# esp_tiny1.net
KiCad netlist of a schematic drawn in EAGLE
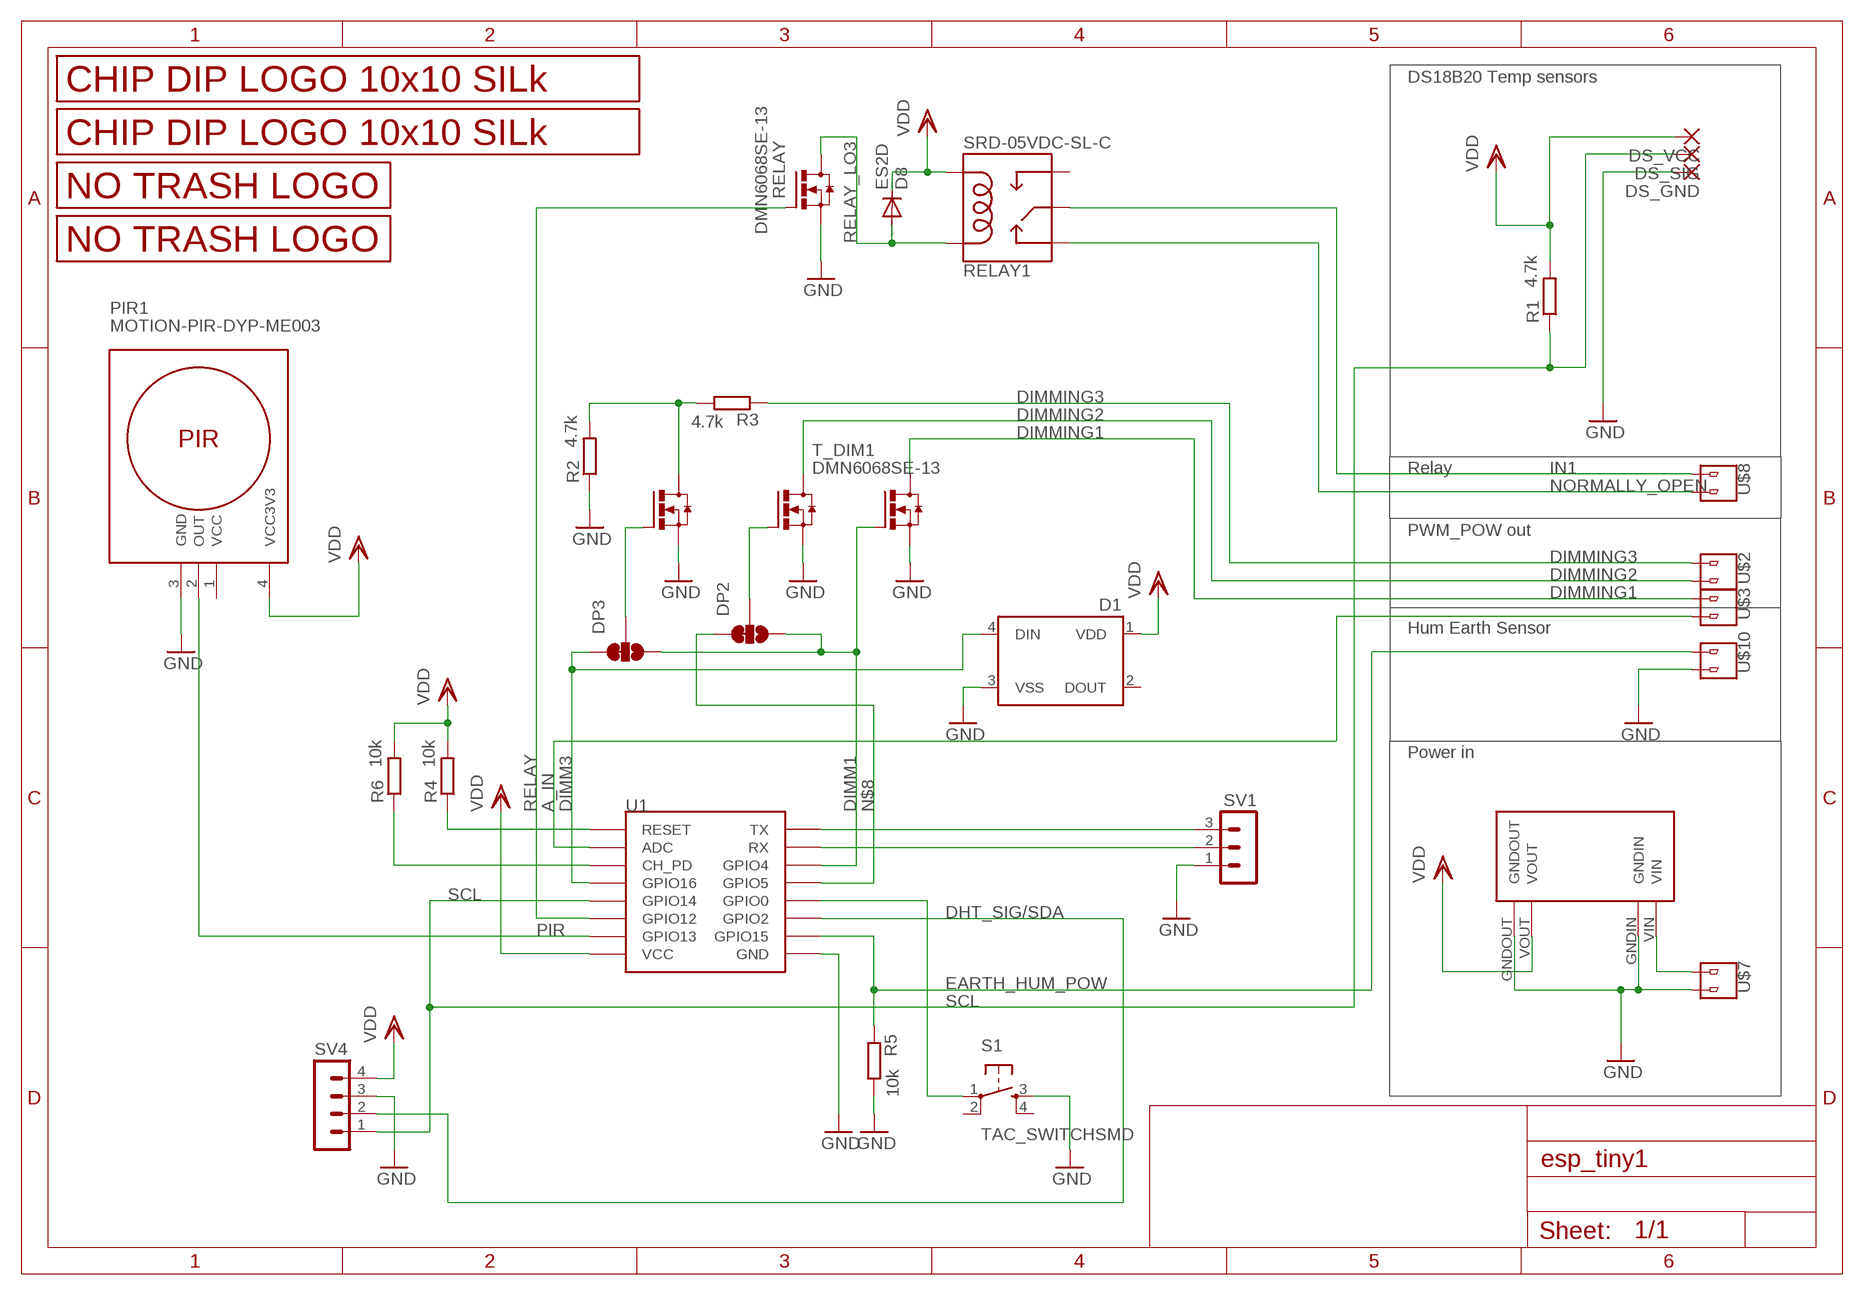
[diagram p0: schematic, sheet 1]

(export (version "E")
  (design (tool "Eeschema 10.0.6"))
  (components
    (comp (ref "D1")
      (value "WS2812B")
      (footprint "eagle-import:WS2812B")
      (libsource (lib "eagle-import") (part "WS2812B"))
    )
    (comp (ref "D8")
      (value "ES2D")
      (footprint "eagle-import:SMB")
      (libsource (lib "eagle-import") (part "DIODE-SMB"))
    )
    (comp (ref "DP2")
      (value "SMD_SJ_3WAY_CLOSED")
      (footprint "eagle-import:SMD_SJ_3WAY_CLOSED")
      (libsource (lib "eagle-import") (part "SMD_SJ_3WAY_CLOSED"))
    )
    (comp (ref "DP3")
      (value "SMD_SJ_3WAY_CLOSED")
      (footprint "eagle-import:SMD_SJ_3WAY_CLOSED")
      (libsource (lib "eagle-import") (part "SMD_SJ_3WAY_CLOSED"))
    )
    (comp (ref "DS_GND")
      (value "SMD2")
      (footprint "eagle-import:SMD1,27-2,54")
      (libsource (lib "eagle-import") (part "SMD2"))
    )
    (comp (ref "DS_SIG")
      (value "SMD2")
      (footprint "eagle-import:SMD1,27-2,54")
      (libsource (lib "eagle-import") (part "SMD2"))
    )
    (comp (ref "DS_VCC")
      (value "SMD2")
      (footprint "eagle-import:SMD1,27-2,54")
      (libsource (lib "eagle-import") (part "SMD2"))
    )
    (comp (ref "PIR1")
      (value "MOTION-PIR-DYP-ME003")
      (footprint "eagle-import:MOTION-PIR-DYP-ME003_FRAMELESS")
      (libsource (lib "eagle-import") (part "MOTION-PIR-DYP-ME003"))
    )
    (comp (ref "R1")
      (value "4.7k")
      (footprint "eagle-import:M0805")
      (libsource (lib "eagle-import") (part "R-EU_M0805"))
    )
    (comp (ref "R2")
      (value "4.7k")
      (footprint "eagle-import:M0805")
      (libsource (lib "eagle-import") (part "R-EU_M0805"))
    )
    (comp (ref "R3")
      (value "4.7k")
      (footprint "eagle-import:M0805")
      (libsource (lib "eagle-import") (part "R-EU_M0805"))
    )
    (comp (ref "R4")
      (value "10k")
      (footprint "eagle-import:M0805")
      (libsource (lib "eagle-import") (part "R-EU_M0805"))
    )
    (comp (ref "R5")
      (value "10k")
      (footprint "eagle-import:M0805")
      (libsource (lib "eagle-import") (part "R-EU_M0805"))
    )
    (comp (ref "R6")
      (value "10k")
      (footprint "eagle-import:M0805")
      (libsource (lib "eagle-import") (part "R-EU_M0805"))
    )
    (comp (ref "RELAY")
      (value "DMN6068SE-13")
      (footprint "eagle-import:SOT223")
      (libsource (lib "eagle-import") (part "NMOSFET_SMD_223"))
    )
    (comp (ref "RELAY1")
      (value "SRD-05VDC-SL-C")
      (footprint "eagle-import:SRD-05VDC-SL-C")
      (libsource (lib "eagle-import") (part "RELAYPTH"))
    )
    (comp (ref "S1")
      (value "TAC_SWITCHSMD")
      (footprint "eagle-import:TACTILE-SWITCH-SMD")
      (libsource (lib "eagle-import") (part "TAC_SWITCHSMD"))
    )
    (comp (ref "SV1")
      (value "MA03-1")
      (footprint "eagle-import:MA03-1")
      (libsource (lib "eagle-import") (part "MA03-1"))
    )
    (comp (ref "SV4")
      (value "MA04-1")
      (footprint "eagle-import:MA04-1")
      (libsource (lib "eagle-import") (part "MA04-1"))
    )
    (comp (ref "T_DIM1")
      (value "DMN6068SE-13")
      (footprint "eagle-import:SOT223")
      (libsource (lib "eagle-import") (part "NMOSFET_SMD_223"))
    )
    (comp (ref "T_DIM2")
      (value "DMN6068SE-13")
      (footprint "eagle-import:SOT223")
      (libsource (lib "eagle-import") (part "NMOSFET_SMD_223"))
    )
    (comp (ref "T_DIM3")
      (value "DMN6068SE-13")
      (footprint "eagle-import:SOT223")
      (libsource (lib "eagle-import") (part "NMOSFET_SMD_223"))
    )
    (comp (ref "U$1")
      (value "LOGO_10X10_SILK")
      (footprint "eagle-import:LOGO2_10X10_SILK")
      (libsource (lib "eagle-import") (part "LOGO_10X10_SILK"))
    )
    (comp (ref "U$2")
      (value "V1")
      (footprint "eagle-import:2_SCREW_PIN")
      (libsource (lib "eagle-import") (part "2_PIN_CONNECTOR"))
    )
    (comp (ref "U$3")
      (value "V1")
      (footprint "eagle-import:2_SCREW_PIN")
      (libsource (lib "eagle-import") (part "2_PIN_CONNECTOR"))
    )
    (comp (ref "U$4")
      (value "LOGO_NO_TRASHNO_TRASH")
      (footprint "eagle-import:LOGO_ROHS_NO_TRASH")
      (libsource (lib "eagle-import") (part "LOGO_NO_TRASHNO_TRASH"))
    )
    (comp (ref "U$7")
      (value "V1")
      (footprint "eagle-import:2_SCREW_PIN")
      (libsource (lib "eagle-import") (part "2_PIN_CONNECTOR"))
    )
    (comp (ref "U$8")
      (value "V1")
      (footprint "eagle-import:2_SCREW_PIN")
      (libsource (lib "eagle-import") (part "2_PIN_CONNECTOR"))
    )
    (comp (ref "U$9")
      (value "LOGO_NO_TRASHROHS")
      (footprint "eagle-import:LOGO_ROHS_SYM")
      (libsource (lib "eagle-import") (part "LOGO_NO_TRASHROHS"))
    )
    (comp (ref "U$10")
      (value "V1")
      (footprint "eagle-import:2_SCREW_PIN")
      (libsource (lib "eagle-import") (part "2_PIN_CONNECTOR"))
    )
    (comp (ref "U$11")
      (value "LOGO_10X10_SILK")
      (footprint "eagle-import:LOGO2_10X10_SILK")
      (libsource (lib "eagle-import") (part "LOGO_10X10_SILK"))
    )
    (comp (ref "U$12")
      (value "MP1584EN")
      (footprint "eagle-import:MP1584EN")
      (libsource (lib "eagle-import") (part "MP1584EN"))
    )
    (comp (ref "U1")
      (value "ESP12SMD")
      (footprint "eagle-import:ESP12-SMD")
      (libsource (lib "eagle-import") (part "ESP12SMD"))
    )
  )
  (nets
    (net (code "1") (name "/A_IN") (class "Default")
      (node (ref "U$3") (pin "P$2") (pinfunction "2_P$2") (pintype "passive"))
      (node (ref "U1") (pin "ADC") (pinfunction "ADC_ADC") (pintype "bidirectional"))
    )
    (net (code "2") (name "/DHT_SIG{slash}SDA") (class "Default")
      (node (ref "SV4") (pin "2") (pinfunction "2_2") (pintype "passive"))
      (node (ref "U1") (pin "GPIO2") (pinfunction "GPIO2_GPIO2") (pintype "bidirectional"))
    )
    (net (code "3") (name "/DIMM1") (class "Default")
      (node (ref "DP2") (pin "3") (pinfunction "3_3") (pintype "passive"))
      (node (ref "DP3") (pin "3") (pinfunction "3_3") (pintype "passive"))
      (node (ref "T_DIM1") (pin "1") (pinfunction "G_1") (pintype "passive"))
      (node (ref "U1") (pin "GPIO4") (pinfunction "GPIO4_GPIO4") (pintype "bidirectional"))
    )
    (net (code "4") (name "/DIMM3") (class "Default")
      (node (ref "D1") (pin "4") (pinfunction "DIN_4") (pintype "input"))
      (node (ref "DP3") (pin "1") (pinfunction "1_1") (pintype "passive"))
      (node (ref "U1") (pin "GPIO16") (pinfunction "GPIO16_GPIO16") (pintype "bidirectional"))
    )
    (net (code "5") (name "/DIMMING1") (class "Default")
      (node (ref "T_DIM1") (pin "2") (pinfunction "D_2") (pintype "passive"))
      (node (ref "T_DIM1") (pin "4") (pinfunction "D_4") (pintype "passive"))
      (node (ref "U$3") (pin "P$1") (pinfunction "1_P$1") (pintype "passive"))
    )
    (net (code "6") (name "/DIMMING2") (class "Default")
      (node (ref "T_DIM2") (pin "2") (pinfunction "D_2") (pintype "passive"))
      (node (ref "T_DIM2") (pin "4") (pinfunction "D_4") (pintype "passive"))
      (node (ref "U$2") (pin "P$2") (pinfunction "2_P$2") (pintype "passive"))
    )
    (net (code "7") (name "/DIMMING3") (class "Default")
      (node (ref "R3") (pin "1") (pinfunction "1_1") (pintype "passive"))
      (node (ref "U$2") (pin "P$1") (pinfunction "1_P$1") (pintype "passive"))
    )
    (net (code "8") (name "/EARTH_HUM_POW") (class "Default")
      (node (ref "R5") (pin "1") (pinfunction "1_1") (pintype "passive"))
      (node (ref "U$10") (pin "P$1") (pinfunction "1_P$1") (pintype "passive"))
      (node (ref "U1") (pin "GPIO15") (pinfunction "GPIO15_GPIO15") (pintype "bidirectional"))
    )
    (net (code "9") (name "/IN1") (class "Default")
      (node (ref "RELAY1") (pin "SWCOMMON") (pinfunction "SWCOMMON_SWCOMMON") (pintype "bidirectional"))
      (node (ref "U$8") (pin "P$1") (pinfunction "1_P$1") (pintype "passive"))
    )
    (net (code "10") (name "/N$8") (class "Default")
      (node (ref "DP2") (pin "1") (pinfunction "1_1") (pintype "passive"))
      (node (ref "U1") (pin "GPIO5") (pinfunction "GPIO5_GPIO5") (pintype "bidirectional"))
    )
    (net (code "11") (name "/NORMALLY_OPEN") (class "Default")
      (node (ref "RELAY1") (pin "SWCLOSED") (pinfunction "SWCLOSE_SWCLOSED") (pintype "bidirectional"))
      (node (ref "U$8") (pin "P$2") (pinfunction "2_P$2") (pintype "passive"))
    )
    (net (code "12") (name "/PIR") (class "Default")
      (node (ref "PIR1") (pin "2") (pinfunction "OUT_2") (pintype "output"))
      (node (ref "U1") (pin "GPIO13") (pinfunction "GPIO13_GPIO13") (pintype "bidirectional"))
    )
    (net (code "13") (name "/RELAY") (class "Default")
      (node (ref "RELAY") (pin "1") (pinfunction "G_1") (pintype "passive"))
      (node (ref "U1") (pin "GPIO12") (pinfunction "GPIO12_GPIO12") (pintype "bidirectional"))
    )
    (net (code "14") (name "/RELAY_LO3") (class "Default")
      (node (ref "D8") (pin "A") (pinfunction "A_A") (pintype "passive"))
      (node (ref "RELAY") (pin "2") (pinfunction "D_2") (pintype "passive"))
      (node (ref "RELAY") (pin "4") (pinfunction "D_4") (pintype "passive"))
      (node (ref "RELAY1") (pin "COIL1") (pinfunction "COIL1_COIL1") (pintype "bidirectional"))
    )
    (net (code "15") (name "/SCL") (class "Default")
      (node (ref "DS_SIG") (pin "1") (pinfunction "P_1") (pintype "passive"))
      (node (ref "R1") (pin "1") (pinfunction "1_1") (pintype "passive"))
      (node (ref "SV4") (pin "1") (pinfunction "1_1") (pintype "passive"))
      (node (ref "U1") (pin "GPIO14") (pinfunction "GPIO14_GPIO14") (pintype "bidirectional"))
    )
    (net (code "16") (name "/VCC") (class "Default")
      (node (ref "PIR1") (pin "1") (pinfunction "VCC_1") (pintype "power_in"))
    )
    (net (code "17") (name "GND") (class "Default")
      (node (ref "D1") (pin "3") (pinfunction "VSS_3") (pintype "power_in"))
      (node (ref "DS_GND") (pin "1") (pinfunction "P_1") (pintype "passive"))
      (node (ref "PIR1") (pin "3") (pinfunction "GND_3") (pintype "power_in"))
      (node (ref "R2") (pin "1") (pinfunction "1_1") (pintype "passive"))
      (node (ref "R5") (pin "2") (pinfunction "2_2") (pintype "passive"))
      (node (ref "RELAY") (pin "3") (pinfunction "S_3") (pintype "passive"))
      (node (ref "S1") (pin "3") (pinfunction "3_3") (pintype "passive"))
      (node (ref "SV1") (pin "1") (pinfunction "1_1") (pintype "passive"))
      (node (ref "SV4") (pin "3") (pinfunction "3_3") (pintype "passive"))
      (node (ref "T_DIM1") (pin "3") (pinfunction "S_3") (pintype "passive"))
      (node (ref "T_DIM2") (pin "3") (pinfunction "S_3") (pintype "passive"))
      (node (ref "T_DIM3") (pin "3") (pinfunction "S_3") (pintype "passive"))
      (node (ref "U$10") (pin "P$2") (pinfunction "2_P$2") (pintype "passive"))
      (node (ref "U$12") (pin "GNDIN") (pinfunction "GNDIN_GNDIN") (pintype "power_in"))
      (node (ref "U$12") (pin "GNDOUT") (pinfunction "GNDOUT_GNDOUT") (pintype "power_in"))
      (node (ref "U$7") (pin "P$2") (pinfunction "2_P$2") (pintype "passive"))
      (node (ref "U1") (pin "GND") (pinfunction "GND_GND") (pintype "bidirectional"))
    )
    (net (code "18") (name "Net-(R2-Pad2)") (class "Default")
      (node (ref "R2") (pin "2") (pinfunction "2_2") (pintype "passive"))
      (node (ref "R3") (pin "2") (pinfunction "2_2") (pintype "passive"))
      (node (ref "T_DIM3") (pin "2") (pinfunction "D_2") (pintype "passive"))
      (node (ref "T_DIM3") (pin "4") (pinfunction "D_4") (pintype "passive"))
    )
    (net (code "19") (name "Net-(R4-Pad1)") (class "Default")
      (node (ref "R4") (pin "1") (pinfunction "1_1") (pintype "passive"))
      (node (ref "U1") (pin "RESET") (pinfunction "RESET_RESET") (pintype "bidirectional"))
    )
    (net (code "20") (name "Net-(R6-Pad1)") (class "Default")
      (node (ref "R6") (pin "1") (pinfunction "1_1") (pintype "passive"))
      (node (ref "U1") (pin "CH_PD") (pinfunction "CH_PD_CH_PD") (pintype "bidirectional"))
    )
    (net (code "21") (name "Net-(S1-Pad1)") (class "Default")
      (node (ref "S1") (pin "1") (pinfunction "1_1") (pintype "passive"))
      (node (ref "U1") (pin "GPIO0") (pinfunction "GPIO0_GPIO0") (pintype "bidirectional"))
    )
    (net (code "22") (name "Net-(T_DIM2-G)") (class "Default")
      (node (ref "DP2") (pin "2") (pinfunction "2_2") (pintype "passive"))
      (node (ref "T_DIM2") (pin "1") (pinfunction "G_1") (pintype "passive"))
    )
    (net (code "23") (name "Net-(T_DIM3-G)") (class "Default")
      (node (ref "DP3") (pin "2") (pinfunction "2_2") (pintype "passive"))
      (node (ref "T_DIM3") (pin "1") (pinfunction "G_1") (pintype "passive"))
    )
    (net (code "24") (name "Net-(U$7-1)") (class "Default")
      (node (ref "U$12") (pin "VIN") (pinfunction "VIN_VIN") (pintype "power_in"))
      (node (ref "U$7") (pin "P$1") (pinfunction "1_P$1") (pintype "passive"))
    )
    (net (code "25") (name "Net-(U1-RX)") (class "Default")
      (node (ref "SV1") (pin "2") (pinfunction "2_2") (pintype "passive"))
      (node (ref "U1") (pin "RXD0") (pinfunction "RX_RXD0") (pintype "bidirectional"))
    )
    (net (code "26") (name "Net-(U1-TX)") (class "Default")
      (node (ref "SV1") (pin "3") (pinfunction "3_3") (pintype "passive"))
      (node (ref "U1") (pin "TXD0") (pinfunction "TX_TXD0") (pintype "bidirectional"))
    )
    (net (code "27") (name "VDD") (class "Default")
      (node (ref "D1") (pin "1") (pinfunction "VDD_1") (pintype "power_in"))
      (node (ref "D8") (pin "C") (pinfunction "C_C") (pintype "passive"))
      (node (ref "DS_VCC") (pin "1") (pinfunction "P_1") (pintype "passive"))
      (node (ref "PIR1") (pin "4") (pinfunction "VCC3V3_4") (pintype "power_in"))
      (node (ref "R1") (pin "2") (pinfunction "2_2") (pintype "passive"))
      (node (ref "R4") (pin "2") (pinfunction "2_2") (pintype "passive"))
      (node (ref "R6") (pin "2") (pinfunction "2_2") (pintype "passive"))
      (node (ref "RELAY1") (pin "COIL0") (pinfunction "COIL0_COIL0") (pintype "bidirectional"))
      (node (ref "SV4") (pin "4") (pinfunction "4_4") (pintype "passive"))
      (node (ref "U$12") (pin "VOUT") (pinfunction "VOUT_VOUT") (pintype "power_in"))
      (node (ref "U1") (pin "VCC") (pinfunction "VCC_VCC") (pintype "bidirectional"))
    )
    (net (code "28") (name "unconnected-(D1-DOUT-Pad2)") (class "Default")
      (node (ref "D1") (pin "2") (pinfunction "DOUT_2") (pintype "output"))
    )
    (net (code "29") (name "unconnected-(RELAY1-PadSWOPEN)") (class "Default")
      (node (ref "RELAY1") (pin "SWOPEN") (pinfunction "SWOPEN_SWOPEN") (pintype "bidirectional"))
    )
    (net (code "30") (name "unconnected-(S1-Pad2)") (class "Default")
      (node (ref "S1") (pin "2") (pinfunction "2_2") (pintype "passive"))
    )
    (net (code "31") (name "unconnected-(S1-Pad4)") (class "Default")
      (node (ref "S1") (pin "4") (pinfunction "4_4") (pintype "passive"))
    )
  )
)
